# KMO_IO_MV2_0.net
KiCad netlist of a schematic drawn in EAGLE
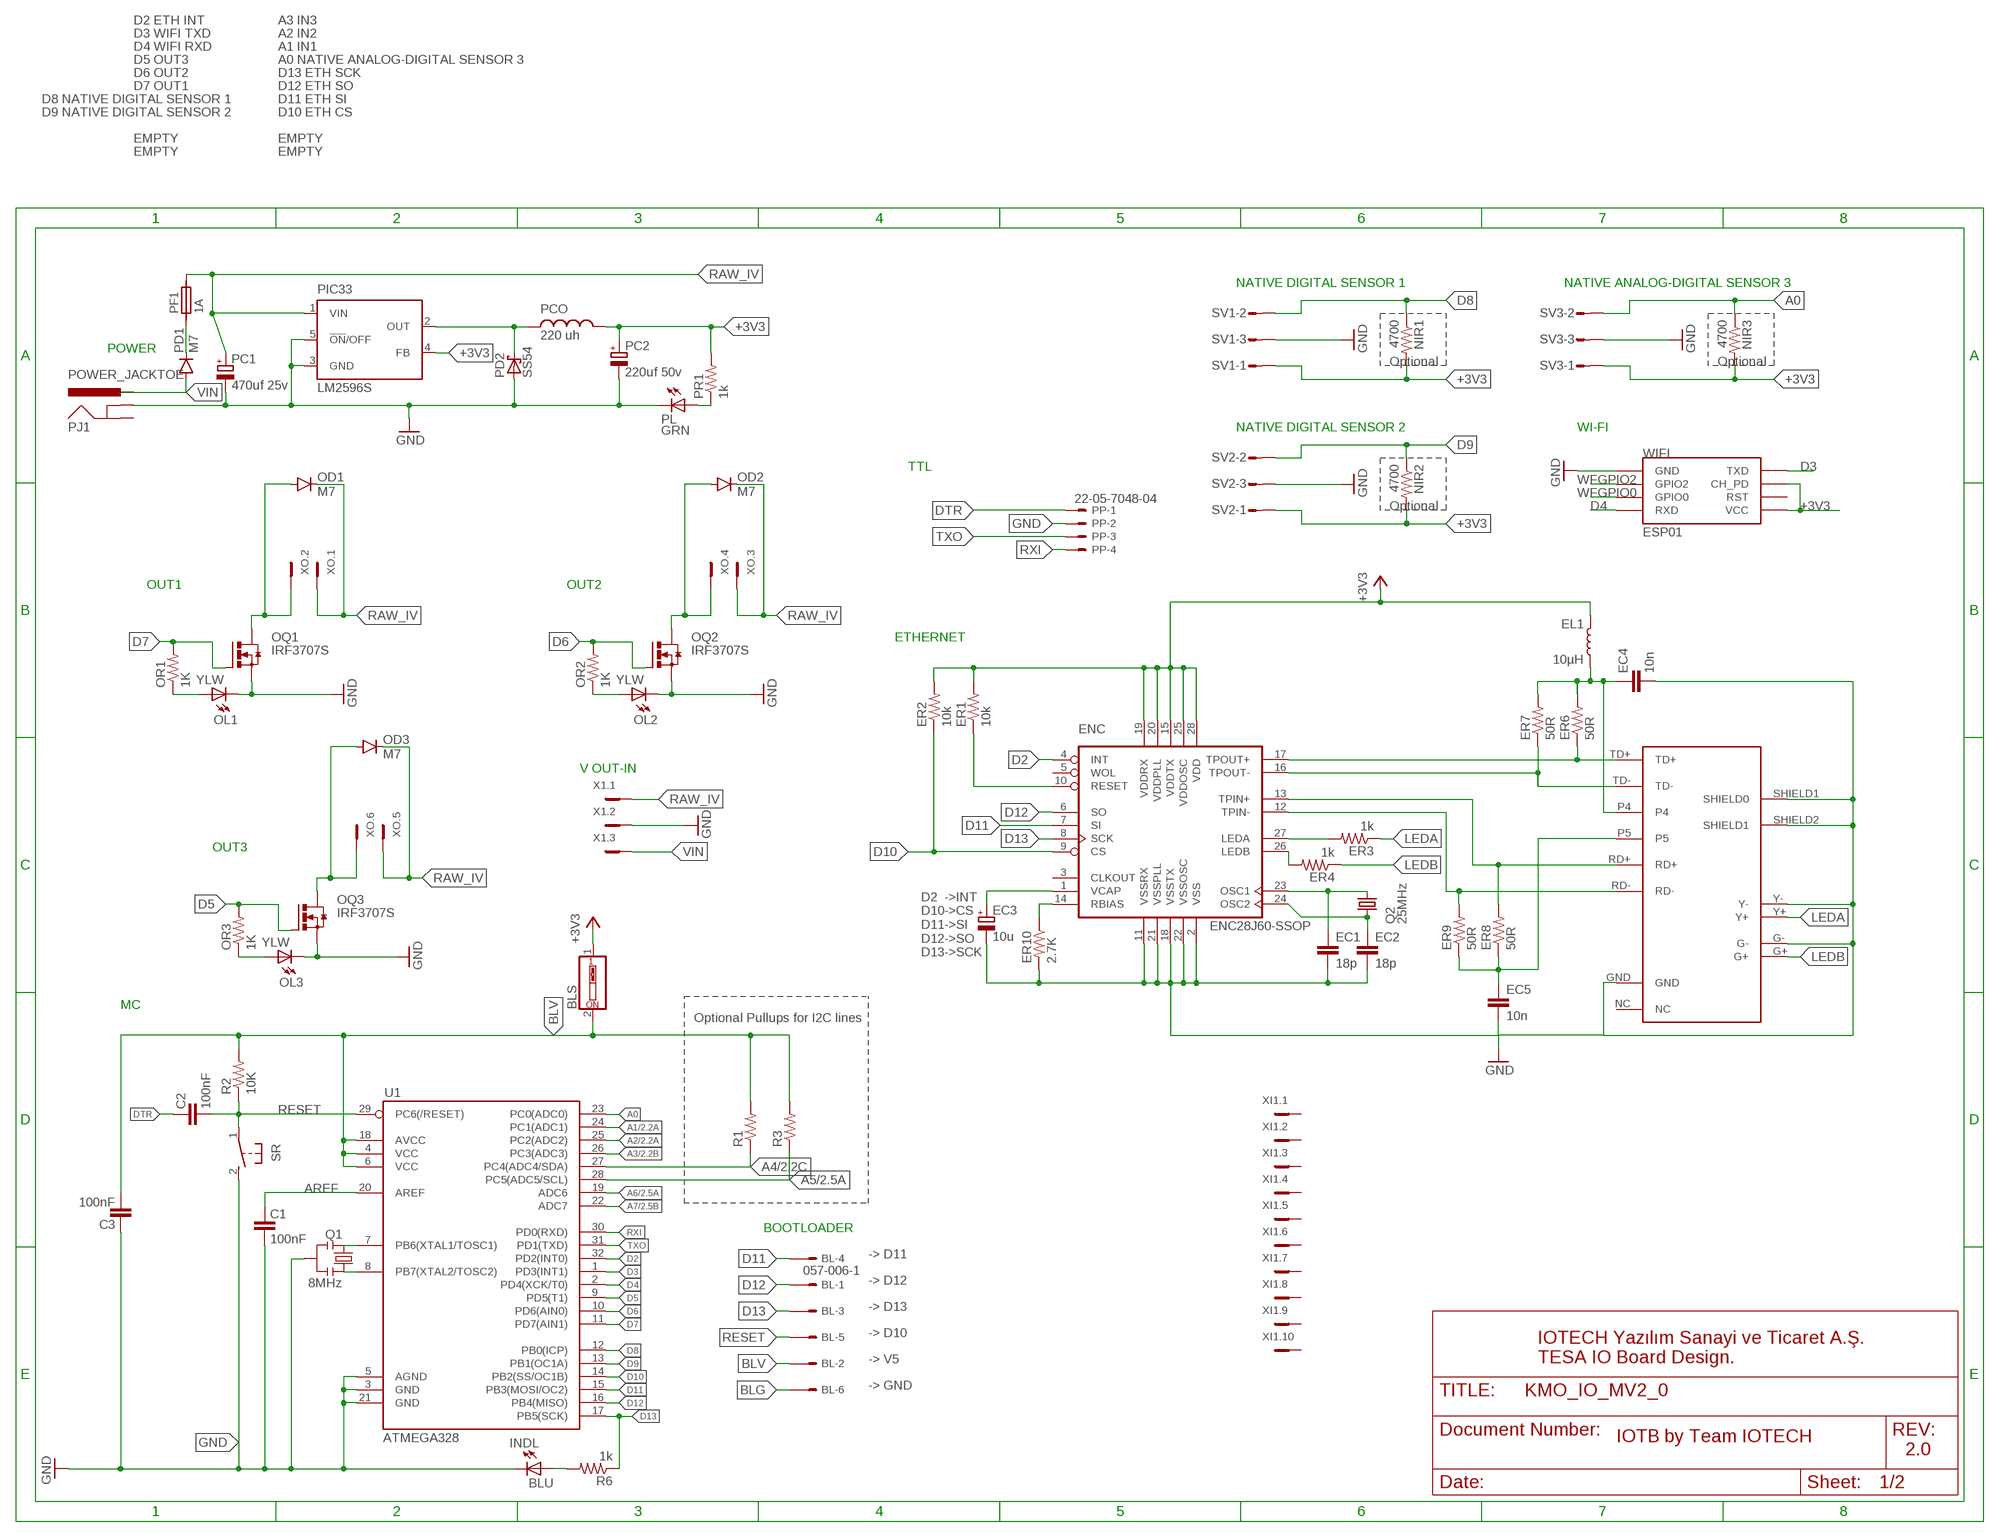
[diagram p0: schematic, sheet 1]
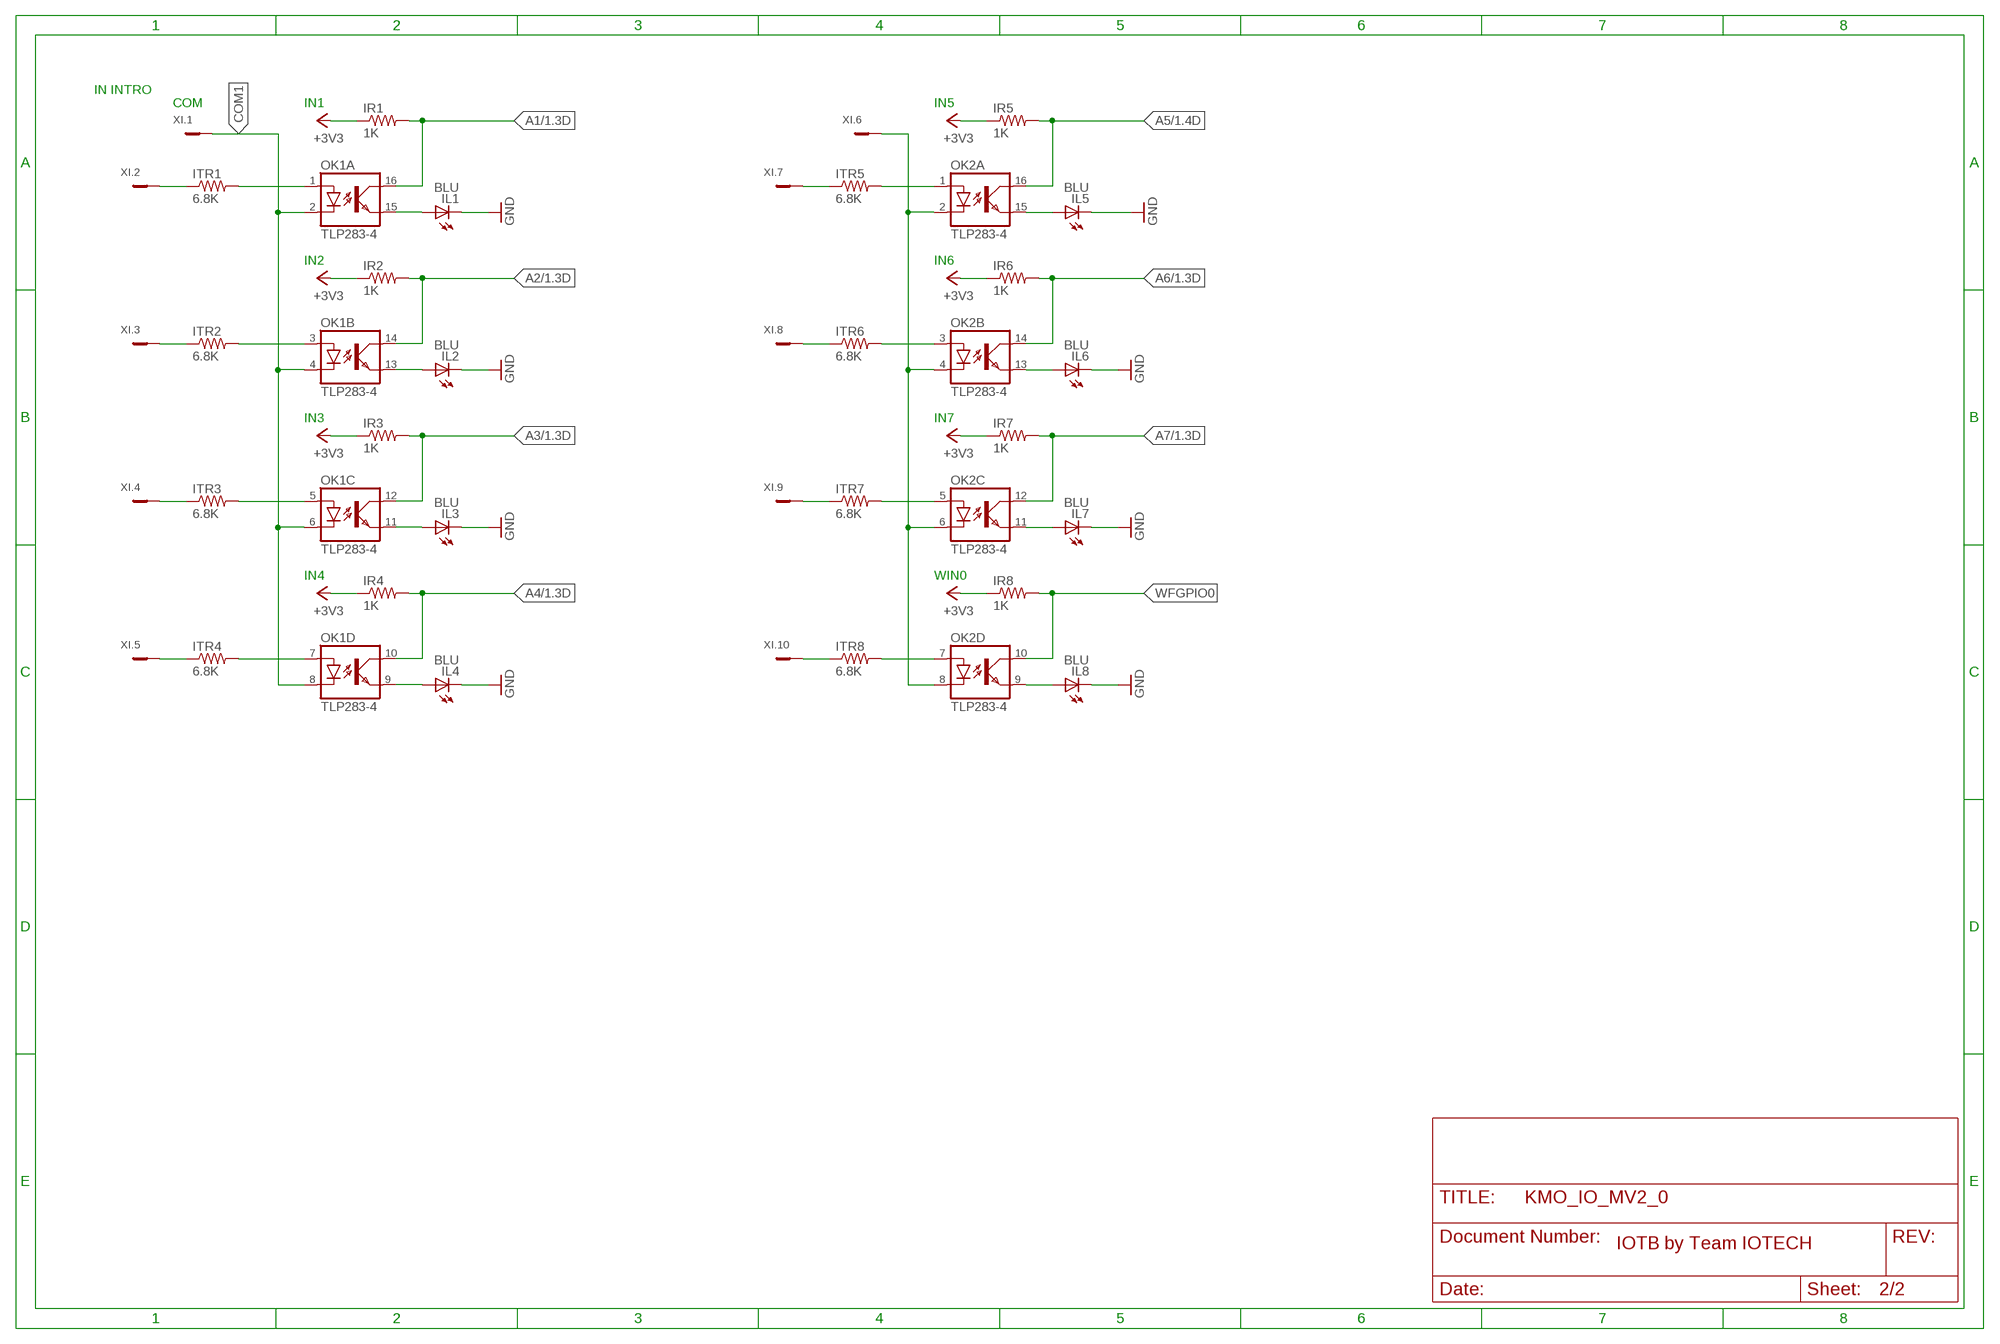
[diagram p1: schematic, sheet 2]

(export (version "E")
  (design (tool "Eeschema 10.0.6"))
  (components
    (comp (ref "BL")
      (value "057-006-1")
      (footprint "eagle-import:057-006-1")
      (libsource (lib "eagle-import") (part "057-006-1"))
    )
    (comp (ref "BLS")
      (value "SW_DIP-1")
      (footprint "eagle-import:EDG-01")
      (libsource (lib "eagle-import") (part "SW_DIP-1"))
    )
    (comp (ref "C1")
      (value "100nF")
      (footprint "eagle-import:0805")
      (libsource (lib "eagle-import") (part "CAP0805"))
    )
    (comp (ref "C2")
      (value "100nF")
      (footprint "eagle-import:0805")
      (libsource (lib "eagle-import") (part "CAP0805"))
    )
    (comp (ref "C3")
      (value "100nF")
      (footprint "eagle-import:0805")
      (libsource (lib "eagle-import") (part "CAP0805"))
    )
    (comp (ref "EC1")
      (value "18p")
      (footprint "eagle-import:0805")
      (libsource (lib "eagle-import") (part "CAP0805"))
    )
    (comp (ref "EC2")
      (value "18p")
      (footprint "eagle-import:0805")
      (libsource (lib "eagle-import") (part "CAP0805"))
    )
    (comp (ref "EC3")
      (value "10u")
      (footprint "eagle-import:CT3216")
      (libsource (lib "eagle-import") (part "CPOL-EUCT3216"))
    )
    (comp (ref "EC4")
      (value "10n")
      (footprint "eagle-import:0805")
      (libsource (lib "eagle-import") (part "CAP0805"))
    )
    (comp (ref "EC5")
      (value "10n")
      (footprint "eagle-import:0805")
      (libsource (lib "eagle-import") (part "CAP0805"))
    )
    (comp (ref "EL1")
      (value "10µH")
      (footprint "eagle-import:0805")
      (libsource (lib "eagle-import") (part "INDUCTOR-0805-3.3UH"))
    )
    (comp (ref "ENC")
      (value "ENC28J60-SSOP")
      (footprint "eagle-import:SSOP28")
      (libsource (lib "eagle-import") (part "ENC28J60-SSOP"))
    )
    (comp (ref "ER1")
      (value "10k")
      (footprint "eagle-import:0805")
      (libsource (lib "eagle-import") (part "RESISTOR0805-RES"))
    )
    (comp (ref "ER2")
      (value "10k")
      (footprint "eagle-import:0805")
      (libsource (lib "eagle-import") (part "RESISTOR0805-RES"))
    )
    (comp (ref "ER3")
      (value "1k")
      (footprint "eagle-import:0805")
      (libsource (lib "eagle-import") (part "RESISTOR0805-RES"))
    )
    (comp (ref "ER4")
      (value "1k")
      (footprint "eagle-import:0805")
      (libsource (lib "eagle-import") (part "RESISTOR0805-RES"))
    )
    (comp (ref "ER6")
      (value "50R")
      (footprint "eagle-import:0805")
      (libsource (lib "eagle-import") (part "RESISTOR0805-RES"))
    )
    (comp (ref "ER7")
      (value "50R")
      (footprint "eagle-import:0805")
      (libsource (lib "eagle-import") (part "RESISTOR0805-RES"))
    )
    (comp (ref "ER8")
      (value "50R")
      (footprint "eagle-import:0805")
      (libsource (lib "eagle-import") (part "RESISTOR0805-RES"))
    )
    (comp (ref "ER9")
      (value "50R")
      (footprint "eagle-import:0805")
      (libsource (lib "eagle-import") (part "RESISTOR0805-RES"))
    )
    (comp (ref "ER10")
      (value "2.7K")
      (footprint "eagle-import:0805")
      (libsource (lib "eagle-import") (part "RESISTOR0805-RES"))
    )
    (comp (ref "INDL")
      (value "BLU")
      (footprint "eagle-import:CHIP-LED0805")
      (libsource (lib "eagle-import") (part "LEDCHIP-LED0805"))
    )
    (comp (ref "NIR1")
      (value "4700")
      (footprint "eagle-import:0805")
      (libsource (lib "eagle-import") (part "RESISTOR0805-RES"))
    )
    (comp (ref "NIR2")
      (value "4700")
      (footprint "eagle-import:0805")
      (libsource (lib "eagle-import") (part "RESISTOR0805-RES"))
    )
    (comp (ref "NIR3")
      (value "4700")
      (footprint "eagle-import:0805")
      (libsource (lib "eagle-import") (part "RESISTOR0805-RES"))
    )
    (comp (ref "OD1")
      (value "M7")
      (footprint "eagle-import:SMA-DIODE")
      (libsource (lib "eagle-import") (part "DIODESMA"))
    )
    (comp (ref "OD2")
      (value "M7")
      (footprint "eagle-import:SMA-DIODE")
      (libsource (lib "eagle-import") (part "DIODESMA"))
    )
    (comp (ref "OD3")
      (value "M7")
      (footprint "eagle-import:SMA-DIODE")
      (libsource (lib "eagle-import") (part "DIODESMA"))
    )
    (comp (ref "OL1")
      (value "YLW")
      (footprint "eagle-import:CHIP-LED0805")
      (libsource (lib "eagle-import") (part "LEDCHIP-LED0805"))
    )
    (comp (ref "OL2")
      (value "YLW")
      (footprint "eagle-import:CHIP-LED0805")
      (libsource (lib "eagle-import") (part "LEDCHIP-LED0805"))
    )
    (comp (ref "OL3")
      (value "YLW")
      (footprint "eagle-import:CHIP-LED0805")
      (libsource (lib "eagle-import") (part "LEDCHIP-LED0805"))
    )
    (comp (ref "OQ1")
      (value "IRF3707S")
      (footprint "eagle-import:D2PACK")
      (libsource (lib "eagle-import") (part "IRF3704S"))
    )
    (comp (ref "OQ2")
      (value "IRF3707S")
      (footprint "eagle-import:D2PACK")
      (libsource (lib "eagle-import") (part "IRF3704S"))
    )
    (comp (ref "OQ3")
      (value "IRF3707S")
      (footprint "eagle-import:D2PACK")
      (libsource (lib "eagle-import") (part "IRF3704S"))
    )
    (comp (ref "OR1")
      (value "1K")
      (footprint "eagle-import:0805")
      (libsource (lib "eagle-import") (part "RESISTOR0805-RES"))
    )
    (comp (ref "OR2")
      (value "1K")
      (footprint "eagle-import:0805")
      (libsource (lib "eagle-import") (part "RESISTOR0805-RES"))
    )
    (comp (ref "OR3")
      (value "1K")
      (footprint "eagle-import:0805")
      (libsource (lib "eagle-import") (part "RESISTOR0805-RES"))
    )
    (comp (ref "PC1")
      (value "470uf 25v")
      (footprint "eagle-import:140CLH-1010")
      (libsource (lib "eagle-import") (part "CPOL-EU140CLH-1010"))
    )
    (comp (ref "PC2")
      (value "220uf 50v")
      (footprint "eagle-import:140CLH-1010")
      (libsource (lib "eagle-import") (part "CPOL-EU140CLH-1010"))
    )
    (comp (ref "PCO")
      (value "220 uh")
      (footprint "eagle-import:MSS1260")
      (libsource (lib "eagle-import") (part "MSS1260"))
    )
    (comp (ref "PD1")
      (value "M7")
      (footprint "eagle-import:SMA-DIODE")
      (libsource (lib "eagle-import") (part "DIODESMA"))
    )
    (comp (ref "PD2")
      (value "SS54")
      (footprint "eagle-import:SMB")
      (libsource (lib "eagle-import") (part "SCHOTTKY-DIODESMD"))
    )
    (comp (ref "PF1")
      (value "1A")
      (footprint "eagle-import:1820")
      (libsource (lib "eagle-import") (part "SIBA194600"))
    )
    (comp (ref "PIC33")
      (value "LM2596S")
      (footprint "eagle-import:TO263-5")
      (fields (field (name "MF") "NATIONAL SEMICONDUCTOR") (field (name "MPN") "LM2596S-ADJ/NOPB"))
      (libsource (lib "eagle-import") (part "LM2596S"))
    )
    (comp (ref "PJ1")
      (value "POWER_JACKTOE")
      (footprint "eagle-import:POWER_JACK_SMD_OVERPASTE_TOE")
      (libsource (lib "eagle-import") (part "POWER_JACKTOE"))
    )
    (comp (ref "PL")
      (value "GRN")
      (footprint "eagle-import:CHIP-LED0805")
      (libsource (lib "eagle-import") (part "LEDCHIP-LED0805"))
    )
    (comp (ref "PP")
      (value "22-05-7048-04")
      (footprint "eagle-import:7395-04")
      (fields (field (name "MF") "MOLEX"))
      (libsource (lib "eagle-import") (part "22-?-0405-7048"))
    )
    (comp (ref "PR1")
      (value "1k")
      (footprint "eagle-import:0805")
      (libsource (lib "eagle-import") (part "RESISTOR0805-RES"))
    )
    (comp (ref "Q1")
      (value "8MHz")
      (footprint "eagle-import:RESONATOR-SMD-1_1")
      (libsource (lib "eagle-import") (part "RESONATOR1{colon}1"))
    )
    (comp (ref "Q2")
      (value "25MHz")
      (footprint "eagle-import:5.0X3.2_2")
      (libsource (lib "eagle-import") (part "KX-9B"))
    )
    (comp (ref "R1")
      (value "RESISTOR0805-RES")
      (footprint "eagle-import:0805")
      (libsource (lib "eagle-import") (part "RESISTOR0805-RES"))
    )
    (comp (ref "R2")
      (value "10K")
      (footprint "eagle-import:0805")
      (libsource (lib "eagle-import") (part "RESISTOR0805-RES"))
    )
    (comp (ref "R3")
      (value "RESISTOR0805-RES")
      (footprint "eagle-import:0805")
      (libsource (lib "eagle-import") (part "RESISTOR0805-RES"))
    )
    (comp (ref "R6")
      (value "1k")
      (footprint "eagle-import:0805")
      (libsource (lib "eagle-import") (part "RESISTOR0805-RES"))
    )
    (comp (ref "SR")
      (value "31-XX")
      (footprint "eagle-import:B3F-31XX")
      (fields (field (name "MPN") "B3F-3100"))
      (libsource (lib "eagle-import") (part "31-XX"))
    )
    (comp (ref "SV1")
      (value "S03P")
      (footprint "eagle-import:S03P")
      (libsource (lib "eagle-import") (part "S03P"))
    )
    (comp (ref "SV2")
      (value "S03P")
      (footprint "eagle-import:S03P")
      (libsource (lib "eagle-import") (part "S03P"))
    )
    (comp (ref "SV3")
      (value "S03P")
      (footprint "eagle-import:S03P")
      (libsource (lib "eagle-import") (part "S03P"))
    )
    (comp (ref "U$2")
      (value "HR911105A")
      (footprint "eagle-import:RJ45")
      (libsource (lib "eagle-import") (part "HR911105A"))
    )
    (comp (ref "U1")
      (value "ATMEGA328")
      (footprint "eagle-import:TQFP32-08")
      (libsource (lib "eagle-import") (part "ATMEGA168"))
    )
    (comp (ref "WIFI")
      (value "ESP01")
      (footprint "eagle-import:ESP01")
      (libsource (lib "eagle-import") (part "ESP01"))
    )
    (comp (ref "X1")
      (value "MC3")
      (footprint "eagle-import:MC3")
      (libsource (lib "eagle-import") (part "MC3"))
    )
    (comp (ref "XI1")
      (value "MC10")
      (footprint "eagle-import:MC10")
      (libsource (lib "eagle-import") (part "MC10"))
    )
    (comp (ref "XO")
      (value "MC6")
      (footprint "eagle-import:MC6")
      (libsource (lib "eagle-import") (part "MC6"))
    )
    (comp (ref "IL1")
      (value "BLU")
      (footprint "eagle-import:CHIP-LED0805")
      (libsource (lib "eagle-import") (part "LEDCHIP-LED0805"))
    )
    (comp (ref "IL2")
      (value "BLU")
      (footprint "eagle-import:CHIP-LED0805")
      (libsource (lib "eagle-import") (part "LEDCHIP-LED0805"))
    )
    (comp (ref "IL3")
      (value "BLU")
      (footprint "eagle-import:CHIP-LED0805")
      (libsource (lib "eagle-import") (part "LEDCHIP-LED0805"))
    )
    (comp (ref "IL4")
      (value "BLU")
      (footprint "eagle-import:CHIP-LED0805")
      (libsource (lib "eagle-import") (part "LEDCHIP-LED0805"))
    )
    (comp (ref "IL5")
      (value "BLU")
      (footprint "eagle-import:CHIP-LED0805")
      (libsource (lib "eagle-import") (part "LEDCHIP-LED0805"))
    )
    (comp (ref "IL6")
      (value "BLU")
      (footprint "eagle-import:CHIP-LED0805")
      (libsource (lib "eagle-import") (part "LEDCHIP-LED0805"))
    )
    (comp (ref "IL7")
      (value "BLU")
      (footprint "eagle-import:CHIP-LED0805")
      (libsource (lib "eagle-import") (part "LEDCHIP-LED0805"))
    )
    (comp (ref "IL8")
      (value "BLU")
      (footprint "eagle-import:CHIP-LED0805")
      (libsource (lib "eagle-import") (part "LEDCHIP-LED0805"))
    )
    (comp (ref "IR1")
      (value "1K")
      (footprint "eagle-import:0805")
      (libsource (lib "eagle-import") (part "RESISTOR0805-RES"))
    )
    (comp (ref "IR2")
      (value "1K")
      (footprint "eagle-import:0805")
      (libsource (lib "eagle-import") (part "RESISTOR0805-RES"))
    )
    (comp (ref "IR3")
      (value "1K")
      (footprint "eagle-import:0805")
      (libsource (lib "eagle-import") (part "RESISTOR0805-RES"))
    )
    (comp (ref "IR4")
      (value "1K")
      (footprint "eagle-import:0805")
      (libsource (lib "eagle-import") (part "RESISTOR0805-RES"))
    )
    (comp (ref "IR5")
      (value "1K")
      (footprint "eagle-import:0805")
      (libsource (lib "eagle-import") (part "RESISTOR0805-RES"))
    )
    (comp (ref "IR6")
      (value "1K")
      (footprint "eagle-import:0805")
      (libsource (lib "eagle-import") (part "RESISTOR0805-RES"))
    )
    (comp (ref "IR7")
      (value "1K")
      (footprint "eagle-import:0805")
      (libsource (lib "eagle-import") (part "RESISTOR0805-RES"))
    )
    (comp (ref "IR8")
      (value "1K")
      (footprint "eagle-import:0805")
      (libsource (lib "eagle-import") (part "RESISTOR0805-RES"))
    )
    (comp (ref "ITR1")
      (value "6.8K")
      (footprint "eagle-import:0805")
      (libsource (lib "eagle-import") (part "RESISTOR0805-RES"))
    )
    (comp (ref "ITR2")
      (value "6.8K")
      (footprint "eagle-import:0805")
      (libsource (lib "eagle-import") (part "RESISTOR0805-RES"))
    )
    (comp (ref "ITR3")
      (value "6.8K")
      (footprint "eagle-import:0805")
      (libsource (lib "eagle-import") (part "RESISTOR0805-RES"))
    )
    (comp (ref "ITR4")
      (value "6.8K")
      (footprint "eagle-import:0805")
      (libsource (lib "eagle-import") (part "RESISTOR0805-RES"))
    )
    (comp (ref "ITR5")
      (value "6.8K")
      (footprint "eagle-import:0805")
      (libsource (lib "eagle-import") (part "RESISTOR0805-RES"))
    )
    (comp (ref "ITR6")
      (value "6.8K")
      (footprint "eagle-import:0805")
      (libsource (lib "eagle-import") (part "RESISTOR0805-RES"))
    )
    (comp (ref "ITR7")
      (value "6.8K")
      (footprint "eagle-import:0805")
      (libsource (lib "eagle-import") (part "RESISTOR0805-RES"))
    )
    (comp (ref "ITR8")
      (value "6.8K")
      (footprint "eagle-import:0805")
      (libsource (lib "eagle-import") (part "RESISTOR0805-RES"))
    )
    (comp (ref "OK1")
      (value "TLP283-4")
      (footprint "eagle-import:MINI-FLAT-16")
      (libsource (lib "eagle-import") (part "TLP283-4"))
    )
    (comp (ref "OK2")
      (value "TLP283-4")
      (footprint "eagle-import:MINI-FLAT-16")
      (libsource (lib "eagle-import") (part "TLP283-4"))
    )
    (comp (ref "XI")
      (value "MC10")
      (footprint "eagle-import:MC10")
      (libsource (lib "eagle-import") (part "MC10"))
    )
  )
  (nets
    (net (code "1") (name "+3V3") (class "Default")
      (node (ref "BLS") (pin "1") (pinfunction "1_1") (pintype "passive"))
      (node (ref "EL1") (pin "1") (pinfunction "1_1") (pintype "passive"))
      (node (ref "ENC") (pin "15") (pinfunction "VDDTX_15") (pintype "power_in"))
      (node (ref "ENC") (pin "19") (pinfunction "VDDRX_19") (pintype "power_in"))
      (node (ref "ENC") (pin "20") (pinfunction "VDDPLL_20") (pintype "power_in"))
      (node (ref "ENC") (pin "25") (pinfunction "VDDOSC_25") (pintype "power_in"))
      (node (ref "ENC") (pin "28") (pinfunction "VDD_28") (pintype "power_in"))
      (node (ref "ER1") (pin "2") (pinfunction "2_2") (pintype "passive"))
      (node (ref "ER2") (pin "2") (pinfunction "2_2") (pintype "passive"))
      (node (ref "IR1") (pin "1") (pinfunction "1_1") (pintype "passive"))
      (node (ref "IR2") (pin "1") (pinfunction "1_1") (pintype "passive"))
      (node (ref "IR3") (pin "1") (pinfunction "1_1") (pintype "passive"))
      (node (ref "IR4") (pin "1") (pinfunction "1_1") (pintype "passive"))
      (node (ref "IR5") (pin "1") (pinfunction "1_1") (pintype "passive"))
      (node (ref "IR6") (pin "1") (pinfunction "1_1") (pintype "passive"))
      (node (ref "IR7") (pin "1") (pinfunction "1_1") (pintype "passive"))
      (node (ref "IR8") (pin "1") (pinfunction "1_1") (pintype "passive"))
      (node (ref "NIR1") (pin "2") (pinfunction "2_2") (pintype "passive"))
      (node (ref "NIR2") (pin "2") (pinfunction "2_2") (pintype "passive"))
      (node (ref "NIR3") (pin "2") (pinfunction "2_2") (pintype "passive"))
      (node (ref "PC2") (pin "+") (pinfunction "+_+") (pintype "passive"))
      (node (ref "PCO") (pin "P$1") (pinfunction "P$1_P$1") (pintype "passive"))
      (node (ref "PIC33") (pin "4") (pinfunction "FB_4") (pintype "input"))
      (node (ref "PR1") (pin "2") (pinfunction "2_2") (pintype "passive"))
      (node (ref "SV1") (pin "1") (pinfunction "S_1") (pintype "passive"))
      (node (ref "SV2") (pin "1") (pinfunction "S_1") (pintype "passive"))
      (node (ref "SV3") (pin "1") (pinfunction "S_1") (pintype "passive"))
      (node (ref "WIFI") (pin "CH_PD") (pinfunction "CH_PD_CH_PD") (pintype "bidirectional"))
      (node (ref "WIFI") (pin "VCC") (pinfunction "VCC_VCC") (pintype "bidirectional"))
    )
    (net (code "2") (name "A0") (class "Default")
      (node (ref "NIR3") (pin "1") (pinfunction "1_1") (pintype "passive"))
      (node (ref "SV3") (pin "2") (pinfunction "S_2") (pintype "passive"))
      (node (ref "U1") (pin "23") (pinfunction "PC0(ADC0)_23") (pintype "bidirectional"))
    )
    (net (code "3") (name "A1") (class "Default")
      (node (ref "IR1") (pin "2") (pinfunction "2_2") (pintype "passive"))
      (node (ref "OK1") (pin "16") (pinfunction "COL_16") (pintype "passive"))
      (node (ref "U1") (pin "24") (pinfunction "PC1(ADC1)_24") (pintype "bidirectional"))
    )
    (net (code "4") (name "A2") (class "Default")
      (node (ref "IR2") (pin "2") (pinfunction "2_2") (pintype "passive"))
      (node (ref "OK1") (pin "14") (pinfunction "COL_14") (pintype "passive"))
      (node (ref "U1") (pin "25") (pinfunction "PC2(ADC2)_25") (pintype "bidirectional"))
    )
    (net (code "5") (name "A3") (class "Default")
      (node (ref "IR3") (pin "2") (pinfunction "2_2") (pintype "passive"))
      (node (ref "OK1") (pin "12") (pinfunction "COL_12") (pintype "passive"))
      (node (ref "U1") (pin "26") (pinfunction "PC3(ADC3)_26") (pintype "bidirectional"))
    )
    (net (code "6") (name "A4") (class "Default")
      (node (ref "IR4") (pin "2") (pinfunction "2_2") (pintype "passive"))
      (node (ref "OK1") (pin "10") (pinfunction "COL_10") (pintype "passive"))
      (node (ref "R1") (pin "1") (pinfunction "1_1") (pintype "passive"))
      (node (ref "U1") (pin "27") (pinfunction "PC4(ADC4/SDA)_27") (pintype "bidirectional"))
    )
    (net (code "7") (name "A5") (class "Default")
      (node (ref "IR5") (pin "2") (pinfunction "2_2") (pintype "passive"))
      (node (ref "OK2") (pin "16") (pinfunction "COL_16") (pintype "passive"))
      (node (ref "R3") (pin "1") (pinfunction "1_1") (pintype "passive"))
      (node (ref "U1") (pin "28") (pinfunction "PC5(ADC5/SCL)_28") (pintype "bidirectional"))
    )
    (net (code "8") (name "A6") (class "Default")
      (node (ref "IR6") (pin "2") (pinfunction "2_2") (pintype "passive"))
      (node (ref "OK2") (pin "14") (pinfunction "COL_14") (pintype "passive"))
      (node (ref "U1") (pin "19") (pinfunction "ADC6_19") (pintype "bidirectional"))
    )
    (net (code "9") (name "A7") (class "Default")
      (node (ref "IR7") (pin "2") (pinfunction "2_2") (pintype "passive"))
      (node (ref "OK2") (pin "12") (pinfunction "COL_12") (pintype "passive"))
      (node (ref "U1") (pin "22") (pinfunction "ADC7_22") (pintype "bidirectional"))
    )
    (net (code "10") (name "AREF") (class "Default")
      (node (ref "C1") (pin "2") (pinfunction "2_2") (pintype "passive"))
      (node (ref "U1") (pin "20") (pinfunction "AREF_20") (pintype "bidirectional"))
    )
    (net (code "11") (name "BLG") (class "Default")
      (node (ref "BL") (pin "6") (pinfunction "S_6") (pintype "passive"))
    )
    (net (code "12") (name "BLV") (class "Default")
      (node (ref "BL") (pin "2") (pinfunction "S_2") (pintype "passive"))
      (node (ref "BLS") (pin "2") (pinfunction "2_2") (pintype "passive"))
      (node (ref "C3") (pin "1") (pinfunction "1_1") (pintype "passive"))
      (node (ref "R1") (pin "2") (pinfunction "2_2") (pintype "passive"))
      (node (ref "R2") (pin "2") (pinfunction "2_2") (pintype "passive"))
      (node (ref "R3") (pin "2") (pinfunction "2_2") (pintype "passive"))
      (node (ref "U1") (pin "18") (pinfunction "AVCC_18") (pintype "bidirectional"))
      (node (ref "U1") (pin "4") (pinfunction "VCC_4") (pintype "bidirectional"))
      (node (ref "U1") (pin "6") (pinfunction "VCC_6") (pintype "bidirectional"))
    )
    (net (code "13") (name "COM1") (class "Default")
      (node (ref "OK1") (pin "2") (pinfunction "C_2") (pintype "passive"))
      (node (ref "OK1") (pin "4") (pinfunction "C_4") (pintype "passive"))
      (node (ref "OK1") (pin "6") (pinfunction "C_6") (pintype "passive"))
      (node (ref "OK1") (pin "8") (pinfunction "C_8") (pintype "passive"))
      (node (ref "XI") (pin "1") (pinfunction "SK_1") (pintype "passive"))
    )
    (net (code "14") (name "D2") (class "Default")
      (node (ref "ENC") (pin "4") (pinfunction "INT_4") (pintype "output"))
      (node (ref "U1") (pin "32") (pinfunction "PD2(INT0)_32") (pintype "bidirectional"))
    )
    (net (code "15") (name "D3") (class "Default")
      (node (ref "U1") (pin "1") (pinfunction "PD3(INT1)_1") (pintype "bidirectional"))
      (node (ref "WIFI") (pin "TX") (pinfunction "TXD_TX") (pintype "bidirectional"))
    )
    (net (code "16") (name "D4") (class "Default")
      (node (ref "U1") (pin "2") (pinfunction "PD4(XCK/T0)_2") (pintype "bidirectional"))
      (node (ref "WIFI") (pin "RX") (pinfunction "RXD_RX") (pintype "bidirectional"))
    )
    (net (code "17") (name "D5") (class "Default")
      (node (ref "OQ3") (pin "1") (pinfunction "G_1") (pintype "passive"))
      (node (ref "OR3") (pin "2") (pinfunction "2_2") (pintype "passive"))
      (node (ref "U1") (pin "9") (pinfunction "PD5(T1)_9") (pintype "bidirectional"))
    )
    (net (code "18") (name "D6") (class "Default")
      (node (ref "OQ2") (pin "1") (pinfunction "G_1") (pintype "passive"))
      (node (ref "OR2") (pin "2") (pinfunction "2_2") (pintype "passive"))
      (node (ref "U1") (pin "10") (pinfunction "PD6(AIN0)_10") (pintype "bidirectional"))
    )
    (net (code "19") (name "D7") (class "Default")
      (node (ref "OQ1") (pin "1") (pinfunction "G_1") (pintype "passive"))
      (node (ref "OR1") (pin "2") (pinfunction "2_2") (pintype "passive"))
      (node (ref "U1") (pin "11") (pinfunction "PD7(AIN1)_11") (pintype "bidirectional"))
    )
    (net (code "20") (name "D8") (class "Default")
      (node (ref "NIR1") (pin "1") (pinfunction "1_1") (pintype "passive"))
      (node (ref "SV1") (pin "2") (pinfunction "S_2") (pintype "passive"))
      (node (ref "U1") (pin "12") (pinfunction "PB0(ICP)_12") (pintype "bidirectional"))
    )
    (net (code "21") (name "D9") (class "Default")
      (node (ref "NIR2") (pin "1") (pinfunction "1_1") (pintype "passive"))
      (node (ref "SV2") (pin "2") (pinfunction "S_2") (pintype "passive"))
      (node (ref "U1") (pin "13") (pinfunction "PB1(OC1A)_13") (pintype "bidirectional"))
    )
    (net (code "22") (name "D10") (class "Default")
      (node (ref "ENC") (pin "9") (pinfunction "CS_9") (pintype "input"))
      (node (ref "ER2") (pin "1") (pinfunction "1_1") (pintype "passive"))
      (node (ref "U1") (pin "14") (pinfunction "PB2(SS/OC1B)_14") (pintype "bidirectional"))
    )
    (net (code "23") (name "D11") (class "Default")
      (node (ref "BL") (pin "4") (pinfunction "S_4") (pintype "passive"))
      (node (ref "ENC") (pin "7") (pinfunction "SI_7") (pintype "input"))
      (node (ref "U1") (pin "15") (pinfunction "PB3(MOSI/OC2)_15") (pintype "bidirectional"))
    )
    (net (code "24") (name "D12") (class "Default")
      (node (ref "BL") (pin "1") (pinfunction "S_1") (pintype "passive"))
      (node (ref "ENC") (pin "6") (pinfunction "SO_6") (pintype "output"))
      (node (ref "U1") (pin "16") (pinfunction "PB4(MISO)_16") (pintype "bidirectional"))
    )
    (net (code "25") (name "D13") (class "Default")
      (node (ref "BL") (pin "3") (pinfunction "S_3") (pintype "passive"))
      (node (ref "ENC") (pin "8") (pinfunction "SCK_8") (pintype "input"))
      (node (ref "R6") (pin "1") (pinfunction "1_1") (pintype "passive"))
      (node (ref "U1") (pin "17") (pinfunction "PB5(SCK)_17") (pintype "bidirectional"))
    )
    (net (code "26") (name "DTR") (class "Default")
      (node (ref "C2") (pin "2") (pinfunction "2_2") (pintype "passive"))
      (node (ref "PP") (pin "1") (pinfunction "S_1") (pintype "passive"))
    )
    (net (code "27") (name "GND") (class "Default")
      (node (ref "C1") (pin "1") (pinfunction "1_1") (pintype "passive"))
      (node (ref "C3") (pin "2") (pinfunction "2_2") (pintype "passive"))
      (node (ref "EC1") (pin "2") (pinfunction "2_2") (pintype "passive"))
      (node (ref "EC2") (pin "2") (pinfunction "2_2") (pintype "passive"))
      (node (ref "EC3") (pin "-") (pinfunction "-_-") (pintype "passive"))
      (node (ref "EC4") (pin "2") (pinfunction "2_2") (pintype "passive"))
      (node (ref "EC5") (pin "2") (pinfunction "2_2") (pintype "passive"))
      (node (ref "ENC") (pin "11") (pinfunction "VSSRX_11") (pintype "power_in"))
      (node (ref "ENC") (pin "18") (pinfunction "VSSTX_18") (pintype "power_in"))
      (node (ref "ENC") (pin "2") (pinfunction "VSS_2") (pintype "power_in"))
      (node (ref "ENC") (pin "21") (pinfunction "VSSPLL_21") (pintype "power_in"))
      (node (ref "ENC") (pin "22") (pinfunction "VSSOSC_22") (pintype "power_in"))
      (node (ref "ER10") (pin "2") (pinfunction "2_2") (pintype "passive"))
      (node (ref "IL1") (pin "C") (pinfunction "C_C") (pintype "passive"))
      (node (ref "IL2") (pin "C") (pinfunction "C_C") (pintype "passive"))
      (node (ref "IL3") (pin "C") (pinfunction "C_C") (pintype "passive"))
      (node (ref "IL4") (pin "C") (pinfunction "C_C") (pintype "passive"))
      (node (ref "IL5") (pin "C") (pinfunction "C_C") (pintype "passive"))
      (node (ref "IL6") (pin "C") (pinfunction "C_C") (pintype "passive"))
      (node (ref "IL7") (pin "C") (pinfunction "C_C") (pintype "passive"))
      (node (ref "IL8") (pin "C") (pinfunction "C_C") (pintype "passive"))
      (node (ref "INDL") (pin "C") (pinfunction "C_C") (pintype "passive"))
      (node (ref "OL1") (pin "C") (pinfunction "C_C") (pintype "passive"))
      (node (ref "OL2") (pin "C") (pinfunction "C_C") (pintype "passive"))
      (node (ref "OL3") (pin "C") (pinfunction "C_C") (pintype "passive"))
      (node (ref "OQ1") (pin "3") (pinfunction "S_3") (pintype "passive"))
      (node (ref "OQ2") (pin "3") (pinfunction "S_3") (pintype "passive"))
      (node (ref "OQ3") (pin "3") (pinfunction "S_3") (pintype "passive"))
      (node (ref "PC1") (pin "-") (pinfunction "-_-") (pintype "passive"))
      (node (ref "PC2") (pin "-") (pinfunction "-_-") (pintype "passive"))
      (node (ref "PD2") (pin "A") (pinfunction "A_A") (pintype "passive"))
      (node (ref "PIC33") (pin "3") (pinfunction "GND_3") (pintype "power_in"))
      (node (ref "PIC33") (pin "5") (pinfunction "~{ON}/OFF_5") (pintype "input"))
      (node (ref "PJ1") (pin "GND") (pinfunction "GNDBREAK_GND") (pintype "bidirectional"))
      (node (ref "PL") (pin "C") (pinfunction "C_C") (pintype "passive"))
      (node (ref "PP") (pin "2") (pinfunction "S_2") (pintype "passive"))
      (node (ref "Q1") (pin "2") (pinfunction "2_2") (pintype "passive"))
      (node (ref "SR") (pin "2") (pinfunction "S_2") (pintype "passive"))
      (node (ref "SV1") (pin "3") (pinfunction "S_3") (pintype "passive"))
      (node (ref "SV2") (pin "3") (pinfunction "S_3") (pintype "passive"))
      (node (ref "SV3") (pin "3") (pinfunction "S_3") (pintype "passive"))
      (node (ref "U$2") (pin "G-") (pinfunction "G-_G-") (pintype "bidirectional"))
      (node (ref "U$2") (pin "GND") (pinfunction "GND_GND") (pintype "bidirectional"))
      (node (ref "U$2") (pin "SHIELD1") (pinfunction "SHIELD0_SHIELD1") (pintype "bidirectional"))
      (node (ref "U$2") (pin "SHIELD2") (pinfunction "SHIELD1_SHIELD2") (pintype "bidirectional"))
      (node (ref "U$2") (pin "Y-") (pinfunction "Y-_Y-") (pintype "bidirectional"))
      (node (ref "U1") (pin "21") (pinfunction "GND_21") (pintype "bidirectional"))
      (node (ref "U1") (pin "3") (pinfunction "GND_3") (pintype "bidirectional"))
      (node (ref "U1") (pin "5") (pinfunction "AGND_5") (pintype "bidirectional"))
      (node (ref "WIFI") (pin "GND") (pinfunction "GND_GND") (pintype "bidirectional"))
      (node (ref "X1") (pin "2") (pinfunction "SK_2") (pintype "passive"))
    )
    (net (code "28") (name "LEDA") (class "Default")
      (node (ref "ER3") (pin "1") (pinfunction "1_1") (pintype "passive"))
      (node (ref "U$2") (pin "Y+") (pinfunction "Y+_Y+") (pintype "bidirectional"))
    )
    (net (code "29") (name "LEDB") (class "Default")
      (node (ref "ER4") (pin "1") (pinfunction "1_1") (pintype "passive"))
      (node (ref "U$2") (pin "G+") (pinfunction "G+_G+") (pintype "bidirectional"))
    )
    (net (code "30") (name "Net-(EC4-Pad1)") (class "Default")
      (node (ref "EC4") (pin "1") (pinfunction "1_1") (pintype "passive"))
      (node (ref "EL1") (pin "2") (pinfunction "2_2") (pintype "passive"))
      (node (ref "ER6") (pin "2") (pinfunction "2_2") (pintype "passive"))
      (node (ref "ER7") (pin "2") (pinfunction "2_2") (pintype "passive"))
      (node (ref "U$2") (pin "P4") (pinfunction "P4_P4") (pintype "bidirectional"))
    )
    (net (code "31") (name "Net-(EC5-Pad1)") (class "Default")
      (node (ref "EC5") (pin "1") (pinfunction "1_1") (pintype "passive"))
      (node (ref "ER8") (pin "1") (pinfunction "1_1") (pintype "passive"))
      (node (ref "ER9") (pin "1") (pinfunction "1_1") (pintype "passive"))
      (node (ref "U$2") (pin "P5") (pinfunction "P5_P5") (pintype "bidirectional"))
    )
    (net (code "32") (name "Net-(ENC-LEDA)") (class "Default")
      (node (ref "ENC") (pin "27") (pinfunction "LEDA_27") (pintype "output"))
      (node (ref "ER3") (pin "2") (pinfunction "2_2") (pintype "passive"))
    )
    (net (code "33") (name "Net-(ENC-LEDB)") (class "Default")
      (node (ref "ENC") (pin "26") (pinfunction "LEDB_26") (pintype "output"))
      (node (ref "ER4") (pin "2") (pinfunction "2_2") (pintype "passive"))
    )
    (net (code "34") (name "Net-(ENC-OSC1)") (class "Default")
      (node (ref "EC1") (pin "1") (pinfunction "1_1") (pintype "passive"))
      (node (ref "ENC") (pin "23") (pinfunction "OSC1_23") (pintype "input"))
      (node (ref "Q2") (pin "2") (pinfunction "2_2") (pintype "passive"))
    )
    (net (code "35") (name "Net-(ENC-OSC2)") (class "Default")
      (node (ref "EC2") (pin "1") (pinfunction "1_1") (pintype "passive"))
      (node (ref "ENC") (pin "24") (pinfunction "OSC2_24") (pintype "output"))
      (node (ref "Q2") (pin "1") (pinfunction "1_1") (pintype "passive"))
    )
    (net (code "36") (name "Net-(ENC-RBIAS)") (class "Default")
      (node (ref "ENC") (pin "14") (pinfunction "RBIAS_14") (pintype "passive"))
      (node (ref "ER10") (pin "1") (pinfunction "1_1") (pintype "passive"))
    )
    (net (code "37") (name "Net-(ENC-RESET)") (class "Default")
      (node (ref "ENC") (pin "10") (pinfunction "RESET_10") (pintype "input"))
      (node (ref "ER1") (pin "1") (pinfunction "1_1") (pintype "passive"))
    )
    (net (code "38") (name "Net-(ENC-TPIN+)") (class "Default")
      (node (ref "ENC") (pin "13") (pinfunction "TPIN+_13") (pintype "input"))
      (node (ref "ER8") (pin "2") (pinfunction "2_2") (pintype "passive"))
      (node (ref "U$2") (pin "RD+") (pinfunction "RD+_RD+") (pintype "bidirectional"))
    )
    (net (code "39") (name "Net-(ENC-TPIN-)") (class "Default")
      (node (ref "ENC") (pin "12") (pinfunction "TPIN-_12") (pintype "input"))
      (node (ref "ER9") (pin "2") (pinfunction "2_2") (pintype "passive"))
      (node (ref "U$2") (pin "RD-") (pinfunction "RD-_RD-") (pintype "bidirectional"))
    )
    (net (code "40") (name "Net-(ENC-TPOUT+)") (class "Default")
      (node (ref "ENC") (pin "17") (pinfunction "TPOUT+_17") (pintype "output"))
      (node (ref "ER6") (pin "1") (pinfunction "1_1") (pintype "passive"))
      (node (ref "U$2") (pin "TD+") (pinfunction "TD+_TD+") (pintype "bidirectional"))
    )
    (net (code "41") (name "Net-(ENC-TPOUT-)") (class "Default")
      (node (ref "ENC") (pin "16") (pinfunction "TPOUT-_16") (pintype "output"))
      (node (ref "ER7") (pin "1") (pinfunction "1_1") (pintype "passive"))
      (node (ref "U$2") (pin "TD-") (pinfunction "TD-_TD-") (pintype "bidirectional"))
    )
    (net (code "42") (name "Net-(ENC-VCAP)") (class "Default")
      (node (ref "EC3") (pin "+") (pinfunction "+_+") (pintype "passive"))
      (node (ref "ENC") (pin "1") (pinfunction "VCAP_1") (pintype "power_in"))
    )
    (net (code "43") (name "Net-(INDL-PadA)") (class "Default")
      (node (ref "INDL") (pin "A") (pinfunction "A_A") (pintype "passive"))
      (node (ref "R6") (pin "2") (pinfunction "2_2") (pintype "passive"))
    )
    (net (code "44") (name "Net-(OK1A-A)") (class "Default")
      (node (ref "ITR1") (pin "2") (pinfunction "2_2") (pintype "passive"))
      (node (ref "OK1") (pin "1") (pinfunction "A_1") (pintype "passive"))
    )
    (net (code "45") (name "Net-(OK1A-EMIT)") (class "Default")
      (node (ref "IL1") (pin "A") (pinfunction "A_A") (pintype "passive"))
      (node (ref "OK1") (pin "15") (pinfunction "EMIT_15") (pintype "passive"))
    )
    (net (code "46") (name "Net-(OK1B-A)") (class "Default")
      (node (ref "ITR2") (pin "2") (pinfunction "2_2") (pintype "passive"))
      (node (ref "OK1") (pin "3") (pinfunction "A_3") (pintype "passive"))
    )
    (net (code "47") (name "Net-(OK1B-EMIT)") (class "Default")
      (node (ref "IL2") (pin "A") (pinfunction "A_A") (pintype "passive"))
      (node (ref "OK1") (pin "13") (pinfunction "EMIT_13") (pintype "passive"))
    )
    (net (code "48") (name "Net-(OK1C-A)") (class "Default")
      (node (ref "ITR3") (pin "2") (pinfunction "2_2") (pintype "passive"))
      (node (ref "OK1") (pin "5") (pinfunction "A_5") (pintype "passive"))
    )
    (net (code "49") (name "Net-(OK1C-EMIT)") (class "Default")
      (node (ref "IL3") (pin "A") (pinfunction "A_A") (pintype "passive"))
      (node (ref "OK1") (pin "11") (pinfunction "EMIT_11") (pintype "passive"))
    )
    (net (code "50") (name "Net-(OK1D-A)") (class "Default")
      (node (ref "ITR4") (pin "2") (pinfunction "2_2") (pintype "passive"))
      (node (ref "OK1") (pin "7") (pinfunction "A_7") (pintype "passive"))
    )
    (net (code "51") (name "Net-(OK1D-EMIT)") (class "Default")
      (node (ref "IL4") (pin "A") (pinfunction "A_A") (pintype "passive"))
      (node (ref "OK1") (pin "9") (pinfunction "EMIT_9") (pintype "passive"))
    )
    (net (code "52") (name "Net-(OK2A-A)") (class "Default")
      (node (ref "ITR5") (pin "2") (pinfunction "2_2") (pintype "passive"))
      (node (ref "OK2") (pin "1") (pinfunction "A_1") (pintype "passive"))
    )
    (net (code "53") (name "Net-(OK2A-C)") (class "Default")
      (node (ref "OK2") (pin "2") (pinfunction "C_2") (pintype "passive"))
      (node (ref "OK2") (pin "4") (pinfunction "C_4") (pintype "passive"))
      (node (ref "OK2") (pin "6") (pinfunction "C_6") (pintype "passive"))
      (node (ref "OK2") (pin "8") (pinfunction "C_8") (pintype "passive"))
      (node (ref "XI") (pin "6") (pinfunction "SK_6") (pintype "passive"))
    )
    (net (code "54") (name "Net-(OK2A-EMIT)") (class "Default")
      (node (ref "IL5") (pin "A") (pinfunction "A_A") (pintype "passive"))
      (node (ref "OK2") (pin "15") (pinfunction "EMIT_15") (pintype "passive"))
    )
    (net (code "55") (name "Net-(OK2B-A)") (class "Default")
      (node (ref "ITR6") (pin "2") (pinfunction "2_2") (pintype "passive"))
      (node (ref "OK2") (pin "3") (pinfunction "A_3") (pintype "passive"))
    )
    (net (code "56") (name "Net-(OK2B-EMIT)") (class "Default")
      (node (ref "IL6") (pin "A") (pinfunction "A_A") (pintype "passive"))
      (node (ref "OK2") (pin "13") (pinfunction "EMIT_13") (pintype "passive"))
    )
    (net (code "57") (name "Net-(OK2C-A)") (class "Default")
      (node (ref "ITR7") (pin "2") (pinfunction "2_2") (pintype "passive"))
      (node (ref "OK2") (pin "5") (pinfunction "A_5") (pintype "passive"))
    )
    (net (code "58") (name "Net-(OK2C-EMIT)") (class "Default")
      (node (ref "IL7") (pin "A") (pinfunction "A_A") (pintype "passive"))
      (node (ref "OK2") (pin "11") (pinfunction "EMIT_11") (pintype "passive"))
    )
    (net (code "59") (name "Net-(OK2D-A)") (class "Default")
      (node (ref "ITR8") (pin "2") (pinfunction "2_2") (pintype "passive"))
      (node (ref "OK2") (pin "7") (pinfunction "A_7") (pintype "passive"))
    )
    (net (code "60") (name "Net-(OK2D-EMIT)") (class "Default")
      (node (ref "IL8") (pin "A") (pinfunction "A_A") (pintype "passive"))
      (node (ref "OK2") (pin "9") (pinfunction "EMIT_9") (pintype "passive"))
    )
    (net (code "61") (name "Net-(OL1-PadA)") (class "Default")
      (node (ref "OL1") (pin "A") (pinfunction "A_A") (pintype "passive"))
      (node (ref "OR1") (pin "1") (pinfunction "1_1") (pintype "passive"))
    )
    (net (code "62") (name "Net-(OL2-PadA)") (class "Default")
      (node (ref "OL2") (pin "A") (pinfunction "A_A") (pintype "passive"))
      (node (ref "OR2") (pin "1") (pinfunction "1_1") (pintype "passive"))
    )
    (net (code "63") (name "Net-(OL3-PadA)") (class "Default")
      (node (ref "OL3") (pin "A") (pinfunction "A_A") (pintype "passive"))
      (node (ref "OR3") (pin "1") (pinfunction "1_1") (pintype "passive"))
    )
    (net (code "64") (name "Net-(OQ1-D)") (class "Default")
      (node (ref "OD1") (pin "A") (pinfunction "A_A") (pintype "passive"))
      (node (ref "OQ1") (pin "2") (pinfunction "D_2") (pintype "passive"))
      (node (ref "XO") (pin "2") (pinfunction "SK_2") (pintype "passive"))
    )
    (net (code "65") (name "Net-(OQ2-D)") (class "Default")
      (node (ref "OD2") (pin "A") (pinfunction "A_A") (pintype "passive"))
      (node (ref "OQ2") (pin "2") (pinfunction "D_2") (pintype "passive"))
      (node (ref "XO") (pin "4") (pinfunction "SK_4") (pintype "passive"))
    )
    (net (code "66") (name "Net-(OQ3-D)") (class "Default")
      (node (ref "OD3") (pin "A") (pinfunction "A_A") (pintype "passive"))
      (node (ref "OQ3") (pin "2") (pinfunction "D_2") (pintype "passive"))
      (node (ref "XO") (pin "6") (pinfunction "SK_6") (pintype "passive"))
    )
    (net (code "67") (name "Net-(PD1-PadC)") (class "Default")
      (node (ref "PD1") (pin "C") (pinfunction "C_C") (pintype "passive"))
      (node (ref "PF1") (pin "1") (pinfunction "1_1") (pintype "passive"))
    )
    (net (code "68") (name "Net-(PIC33-OUT)") (class "Default")
      (node (ref "PCO") (pin "P$2") (pinfunction "P$2_P$2") (pintype "passive"))
      (node (ref "PD2") (pin "C") (pinfunction "C_C") (pintype "passive"))
      (node (ref "PIC33") (pin "2") (pinfunction "OUT_2") (pintype "output"))
    )
    (net (code "69") (name "Net-(PL-PadA)") (class "Default")
      (node (ref "PL") (pin "A") (pinfunction "A_A") (pintype "passive"))
      (node (ref "PR1") (pin "1") (pinfunction "1_1") (pintype "passive"))
    )
    (net (code "70") (name "Net-(U1-PB6(XTAL1{slash}TOSC1))") (class "Default")
      (node (ref "Q1") (pin "1") (pinfunction "1_1") (pintype "passive"))
      (node (ref "U1") (pin "7") (pinfunction "PB6(XTAL1/TOSC1)_7") (pintype "bidirectional"))
    )
    (net (code "71") (name "Net-(U1-PB7(XTAL2{slash}TOSC2))") (class "Default")
      (node (ref "Q1") (pin "3") (pinfunction "3_3") (pintype "passive"))
      (node (ref "U1") (pin "8") (pinfunction "PB7(XTAL2/TOSC2)_8") (pintype "bidirectional"))
    )
    (net (code "72") (name "Net-(XIB-SK)") (class "Default")
      (node (ref "ITR8") (pin "1") (pinfunction "1_1") (pintype "passive"))
      (node (ref "XI") (pin "10") (pinfunction "SK_10") (pintype "passive"))
    )
    (net (code "73") (name "Net-(XIC-SK)") (class "Default")
      (node (ref "ITR1") (pin "1") (pinfunction "1_1") (pintype "passive"))
      (node (ref "XI") (pin "2") (pinfunction "SK_2") (pintype "passive"))
    )
    (net (code "74") (name "Net-(XID-SK)") (class "Default")
      (node (ref "ITR2") (pin "1") (pinfunction "1_1") (pintype "passive"))
      (node (ref "XI") (pin "3") (pinfunction "SK_3") (pintype "passive"))
    )
    (net (code "75") (name "Net-(XIE-SK)") (class "Default")
      (node (ref "ITR3") (pin "1") (pinfunction "1_1") (pintype "passive"))
      (node (ref "XI") (pin "4") (pinfunction "SK_4") (pintype "passive"))
    )
    (net (code "76") (name "Net-(XIF-SK)") (class "Default")
      (node (ref "ITR4") (pin "1") (pinfunction "1_1") (pintype "passive"))
      (node (ref "XI") (pin "5") (pinfunction "SK_5") (pintype "passive"))
    )
    (net (code "77") (name "Net-(XIH-SK)") (class "Default")
      (node (ref "ITR5") (pin "1") (pinfunction "1_1") (pintype "passive"))
      (node (ref "XI") (pin "7") (pinfunction "SK_7") (pintype "passive"))
    )
    (net (code "78") (name "Net-(XII-SK)") (class "Default")
      (node (ref "ITR6") (pin "1") (pinfunction "1_1") (pintype "passive"))
      (node (ref "XI") (pin "8") (pinfunction "SK_8") (pintype "passive"))
    )
    (net (code "79") (name "Net-(XIJ-SK)") (class "Default")
      (node (ref "ITR7") (pin "1") (pinfunction "1_1") (pintype "passive"))
      (node (ref "XI") (pin "9") (pinfunction "SK_9") (pintype "passive"))
    )
    (net (code "80") (name "RAW_IV") (class "Default")
      (node (ref "OD1") (pin "C") (pinfunction "C_C") (pintype "passive"))
      (node (ref "OD2") (pin "C") (pinfunction "C_C") (pintype "passive"))
      (node (ref "OD3") (pin "C") (pinfunction "C_C") (pintype "passive"))
      (node (ref "PC1") (pin "+") (pinfunction "+_+") (pintype "passive"))
      (node (ref "PF1") (pin "2") (pinfunction "2_2") (pintype "passive"))
      (node (ref "PIC33") (pin "1") (pinfunction "VIN_1") (pintype "input"))
      (node (ref "X1") (pin "1") (pinfunction "SK_1") (pintype "passive"))
      (node (ref "XO") (pin "1") (pinfunction "SK_1") (pintype "passive"))
      (node (ref "XO") (pin "3") (pinfunction "SK_3") (pintype "passive"))
      (node (ref "XO") (pin "5") (pinfunction "SK_5") (pintype "passive"))
    )
    (net (code "81") (name "RESET") (class "Default")
      (node (ref "BL") (pin "5") (pinfunction "S_5") (pintype "passive"))
      (node (ref "C2") (pin "1") (pinfunction "1_1") (pintype "passive"))
      (node (ref "R2") (pin "1") (pinfunction "1_1") (pintype "passive"))
      (node (ref "SR") (pin "1") (pinfunction "P_1") (pintype "passive"))
      (node (ref "U1") (pin "29") (pinfunction "PC6(/RESET)_29") (pintype "bidirectional"))
    )
    (net (code "82") (name "RXI") (class "Default")
      (node (ref "PP") (pin "4") (pinfunction "S_4") (pintype "passive"))
      (node (ref "U1") (pin "30") (pinfunction "PD0(RXD)_30") (pintype "bidirectional"))
    )
    (net (code "83") (name "TXO") (class "Default")
      (node (ref "PP") (pin "3") (pinfunction "S_3") (pintype "passive"))
      (node (ref "U1") (pin "31") (pinfunction "PD1(TXD)_31") (pintype "bidirectional"))
    )
    (net (code "84") (name "VIN") (class "Default")
      (node (ref "PD1") (pin "A") (pinfunction "A_A") (pintype "passive"))
      (node (ref "PJ1") (pin "VIN0") (pinfunction "PWR_VIN0") (pintype "bidirectional"))
      (node (ref "X1") (pin "3") (pinfunction "SK_3") (pintype "passive"))
    )
    (net (code "85") (name "WFGPIO0") (class "Default")
      (node (ref "IR8") (pin "2") (pinfunction "2_2") (pintype "passive"))
      (node (ref "OK2") (pin "10") (pinfunction "COL_10") (pintype "passive"))
      (node (ref "WIFI") (pin "GPIO0") (pinfunction "GPIO0_GPIO0") (pintype "bidirectional"))
    )
    (net (code "86") (name "WFGPIO2") (class "Default")
      (node (ref "WIFI") (pin "GPIO2") (pinfunction "GPIO2_GPIO2") (pintype "bidirectional"))
    )
    (net (code "87") (name "unconnected-(ENC-CLKOUT-Pad3)") (class "Default")
      (node (ref "ENC") (pin "3") (pinfunction "CLKOUT_3") (pintype "output"))
    )
    (net (code "88") (name "unconnected-(ENC-WOL-Pad5)") (class "Default")
      (node (ref "ENC") (pin "5") (pinfunction "WOL_5") (pintype "output"))
    )
    (net (code "89") (name "unconnected-(PJ1-GND-PadP$4)") (class "Default")
      (node (ref "PJ1") (pin "P$4") (pinfunction "GND_P$4") (pintype "bidirectional"))
    )
    (net (code "90") (name "unconnected-(U$2-PadNC)") (class "Default")
      (node (ref "U$2") (pin "NC") (pinfunction "NC_NC") (pintype "bidirectional"))
    )
    (net (code "91") (name "unconnected-(WIFI-PadRST)") (class "Default")
      (node (ref "WIFI") (pin "RST") (pinfunction "RST_RST") (pintype "bidirectional"))
    )
    (net (code "92") (name "unconnected-(XI1A-SK-Pad1)") (class "Default")
      (node (ref "XI1") (pin "1") (pinfunction "SK_1") (pintype "passive"))
    )
    (net (code "93") (name "unconnected-(XI1B-SK-Pad10)") (class "Default")
      (node (ref "XI1") (pin "10") (pinfunction "SK_10") (pintype "passive"))
    )
    (net (code "94") (name "unconnected-(XI1C-SK-Pad2)") (class "Default")
      (node (ref "XI1") (pin "2") (pinfunction "SK_2") (pintype "passive"))
    )
    (net (code "95") (name "unconnected-(XI1D-SK-Pad3)") (class "Default")
      (node (ref "XI1") (pin "3") (pinfunction "SK_3") (pintype "passive"))
    )
    (net (code "96") (name "unconnected-(XI1E-SK-Pad4)") (class "Default")
      (node (ref "XI1") (pin "4") (pinfunction "SK_4") (pintype "passive"))
    )
    (net (code "97") (name "unconnected-(XI1F-SK-Pad5)") (class "Default")
      (node (ref "XI1") (pin "5") (pinfunction "SK_5") (pintype "passive"))
    )
    (net (code "98") (name "unconnected-(XI1G-SK-Pad6)") (class "Default")
      (node (ref "XI1") (pin "6") (pinfunction "SK_6") (pintype "passive"))
    )
    (net (code "99") (name "unconnected-(XI1H-SK-Pad7)") (class "Default")
      (node (ref "XI1") (pin "7") (pinfunction "SK_7") (pintype "passive"))
    )
    (net (code "100") (name "unconnected-(XI1I-SK-Pad8)") (class "Default")
      (node (ref "XI1") (pin "8") (pinfunction "SK_8") (pintype "passive"))
    )
    (net (code "101") (name "unconnected-(XI1J-SK-Pad9)") (class "Default")
      (node (ref "XI1") (pin "9") (pinfunction "SK_9") (pintype "passive"))
    )
  )
)
